# Current_Sense.net
KiCad netlist of a schematic drawn in EAGLE
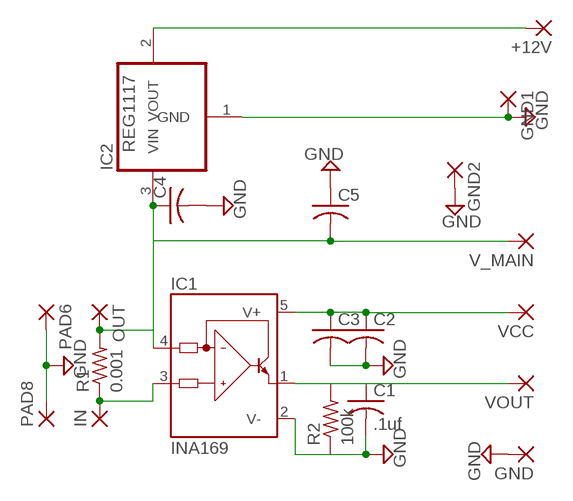
[diagram p0: schematic, sheet 1]

(export (version "E")
  (design (tool "Eeschema 10.0.6"))
  (components
    (comp (ref "+12V")
      (value "SMD2")
      (footprint "eagle-import:SMD1,27-2,54")
      (libsource (lib "eagle-import") (part "SMD2"))
    )
    (comp (ref "C1")
      (value ".1uf")
      (footprint "eagle-import:C0805K")
      (libsource (lib "eagle-import") (part "C-USC0805K"))
    )
    (comp (ref "C2")
      (value "C-USC0805K")
      (footprint "eagle-import:C0805K")
      (libsource (lib "eagle-import") (part "C-USC0805K"))
    )
    (comp (ref "C3")
      (value "C-USC0805K")
      (footprint "eagle-import:C0805K")
      (libsource (lib "eagle-import") (part "C-USC0805K"))
    )
    (comp (ref "C4")
      (value "C-USC0805K")
      (footprint "eagle-import:C0805K")
      (libsource (lib "eagle-import") (part "C-USC0805K"))
    )
    (comp (ref "C5")
      (value "C-USC0805K")
      (footprint "eagle-import:C0805K")
      (libsource (lib "eagle-import") (part "C-USC0805K"))
    )
    (comp (ref "GND")
      (value "SMD2")
      (footprint "eagle-import:SMD1,27-2,54")
      (libsource (lib "eagle-import") (part "SMD2"))
    )
    (comp (ref "GND1")
      (value "SMD2")
      (footprint "eagle-import:SMD1,27-2,54")
      (libsource (lib "eagle-import") (part "SMD2"))
    )
    (comp (ref "GND2")
      (value "SMD2")
      (footprint "eagle-import:SMD1,27-2,54")
      (libsource (lib "eagle-import") (part "SMD2"))
    )
    (comp (ref "IC1")
      (value "INA169")
      (footprint "eagle-import:SOT23-5")
      (fields (field (name "MF") "TEXAS INSTRUMENTS") (field (name "MPN") "INA138NA/250"))
      (libsource (lib "eagle-import") (part "INA138"))
    )
    (comp (ref "IC2")
      (value "REG1117")
      (footprint "eagle-import:SOT223")
      (libsource (lib "eagle-import") (part "REG1117"))
    )
    (comp (ref "IN")
      (value "SMD5")
      (footprint "eagle-import:SMD2,54-5,08")
      (libsource (lib "eagle-import") (part "SMD5"))
    )
    (comp (ref "OUT")
      (value "SMD5")
      (footprint "eagle-import:SMD2,54-5,08")
      (libsource (lib "eagle-import") (part "SMD5"))
    )
    (comp (ref "PAD6")
      (value "SMD5")
      (footprint "eagle-import:SMD2,54-5,08")
      (libsource (lib "eagle-import") (part "SMD5"))
    )
    (comp (ref "PAD8")
      (value "SMD5")
      (footprint "eagle-import:SMD2,54-5,08")
      (libsource (lib "eagle-import") (part "SMD5"))
    )
    (comp (ref "R1")
      (value "0.001")
      (footprint "eagle-import:R2512")
      (libsource (lib "eagle-import") (part "R-US_R2512"))
    )
    (comp (ref "R2")
      (value "100k")
      (footprint "eagle-import:R0805")
      (libsource (lib "eagle-import") (part "R-US_R0805"))
    )
    (comp (ref "VCC")
      (value "SMD2")
      (footprint "eagle-import:SMD1,27-2,54")
      (libsource (lib "eagle-import") (part "SMD2"))
    )
    (comp (ref "VOUT")
      (value "SMD2")
      (footprint "eagle-import:SMD1,27-2,54")
      (libsource (lib "eagle-import") (part "SMD2"))
    )
    (comp (ref "V_MAIN")
      (value "SMD2")
      (footprint "eagle-import:SMD1,27-2,54")
      (libsource (lib "eagle-import") (part "SMD2"))
    )
  )
  (nets
    (net (code "1") (name "GND") (class "Default")
      (node (ref "C1") (pin "2") (pinfunction "2_2") (pintype "passive"))
      (node (ref "C2") (pin "2") (pinfunction "2_2") (pintype "passive"))
      (node (ref "C3") (pin "2") (pinfunction "2_2") (pintype "passive"))
      (node (ref "C4") (pin "2") (pinfunction "2_2") (pintype "passive"))
      (node (ref "C5") (pin "1") (pinfunction "1_1") (pintype "passive"))
      (node (ref "GND") (pin "1") (pinfunction "P_1") (pintype "passive"))
      (node (ref "GND1") (pin "1") (pinfunction "P_1") (pintype "passive"))
      (node (ref "GND2") (pin "1") (pinfunction "P_1") (pintype "passive"))
      (node (ref "IC1") (pin "2") (pinfunction "V-_2") (pintype "power_in"))
      (node (ref "IC2") (pin "1") (pinfunction "GND_1") (pintype "power_in"))
      (node (ref "PAD6") (pin "1") (pinfunction "P_1") (pintype "passive"))
      (node (ref "PAD8") (pin "1") (pinfunction "P_1") (pintype "passive"))
      (node (ref "R2") (pin "1") (pinfunction "1_1") (pintype "passive"))
    )
    (net (code "2") (name "Net-(+12V-P)") (class "Default")
      (node (ref "+12V") (pin "1") (pinfunction "P_1") (pintype "passive"))
      (node (ref "IC2") (pin "2") (pinfunction "VOUT_2") (pintype "output"))
    )
    (net (code "3") (name "Net-(IC1-IN+)") (class "Default")
      (node (ref "IC1") (pin "3") (pinfunction "IN+_3") (pintype "input"))
      (node (ref "IN") (pin "1") (pinfunction "P_1") (pintype "passive"))
      (node (ref "R1") (pin "1") (pinfunction "1_1") (pintype "passive"))
    )
    (net (code "4") (name "Net-(IC1-IN-)") (class "Default")
      (node (ref "C4") (pin "1") (pinfunction "1_1") (pintype "passive"))
      (node (ref "C5") (pin "2") (pinfunction "2_2") (pintype "passive"))
      (node (ref "IC1") (pin "4") (pinfunction "IN-_4") (pintype "input"))
      (node (ref "IC2") (pin "3") (pinfunction "VIN_3") (pintype "input"))
      (node (ref "OUT") (pin "1") (pinfunction "P_1") (pintype "passive"))
      (node (ref "R1") (pin "2") (pinfunction "2_2") (pintype "passive"))
      (node (ref "V_MAIN") (pin "1") (pinfunction "P_1") (pintype "passive"))
    )
    (net (code "5") (name "Net-(IC1-OUT)") (class "Default")
      (node (ref "C1") (pin "1") (pinfunction "1_1") (pintype "passive"))
      (node (ref "IC1") (pin "1") (pinfunction "OUT_1") (pintype "output"))
      (node (ref "R2") (pin "2") (pinfunction "2_2") (pintype "passive"))
      (node (ref "VOUT") (pin "1") (pinfunction "P_1") (pintype "passive"))
    )
    (net (code "6") (name "Net-(IC1-V+)") (class "Default")
      (node (ref "C2") (pin "1") (pinfunction "1_1") (pintype "passive"))
      (node (ref "C3") (pin "1") (pinfunction "1_1") (pintype "passive"))
      (node (ref "IC1") (pin "5") (pinfunction "V+_5") (pintype "power_in"))
      (node (ref "VCC") (pin "1") (pinfunction "P_1") (pintype "passive"))
    )
  )
)
